# adapter_RX2189.net
KiCad netlist of a schematic drawn in EAGLE
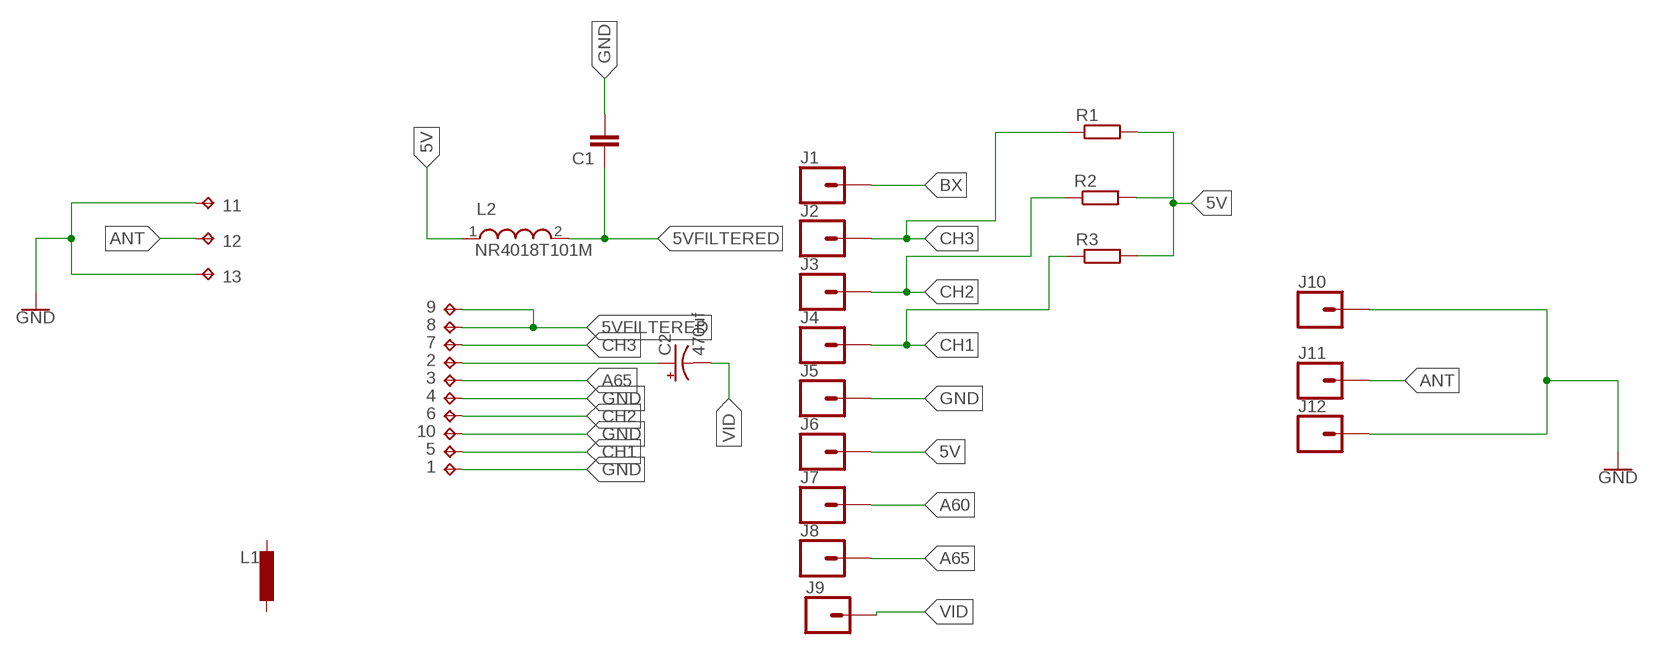
[diagram p0: schematic, sheet 1]

(export (version "E")
  (design (tool "Eeschema 10.0.6"))
  (components
    (comp (ref "1")
      (value "TPTP10SQ")
      (footprint "eagle-import:TP10SQ")
      (libsource (lib "eagle-import") (part "TPTP10SQ"))
    )
    (comp (ref "2")
      (value "TPTP10SQ")
      (footprint "eagle-import:TP10SQ")
      (libsource (lib "eagle-import") (part "TPTP10SQ"))
    )
    (comp (ref "3")
      (value "TPTP10SQ")
      (footprint "eagle-import:TP10SQ")
      (libsource (lib "eagle-import") (part "TPTP10SQ"))
    )
    (comp (ref "4")
      (value "TPTP10SQ")
      (footprint "eagle-import:TP10SQ")
      (libsource (lib "eagle-import") (part "TPTP10SQ"))
    )
    (comp (ref "5")
      (value "TPTP10SQ")
      (footprint "eagle-import:TP10SQ")
      (libsource (lib "eagle-import") (part "TPTP10SQ"))
    )
    (comp (ref "6")
      (value "TPTP10SQ")
      (footprint "eagle-import:TP10SQ")
      (libsource (lib "eagle-import") (part "TPTP10SQ"))
    )
    (comp (ref "7")
      (value "TPTP10SQ")
      (footprint "eagle-import:TP10SQ")
      (libsource (lib "eagle-import") (part "TPTP10SQ"))
    )
    (comp (ref "8")
      (value "TPTP10SQ")
      (footprint "eagle-import:TP10SQ")
      (libsource (lib "eagle-import") (part "TPTP10SQ"))
    )
    (comp (ref "9")
      (value "TPTP10SQ")
      (footprint "eagle-import:TP10SQ")
      (libsource (lib "eagle-import") (part "TPTP10SQ"))
    )
    (comp (ref "10")
      (value "TPTP10SQ")
      (footprint "eagle-import:TP10SQ")
      (libsource (lib "eagle-import") (part "TPTP10SQ"))
    )
    (comp (ref "11")
      (value "TPTP10SQ")
      (footprint "eagle-import:TP10SQ")
      (libsource (lib "eagle-import") (part "TPTP10SQ"))
    )
    (comp (ref "12")
      (value "TPTP10SQ")
      (footprint "eagle-import:TP10SQ")
      (libsource (lib "eagle-import") (part "TPTP10SQ"))
    )
    (comp (ref "13")
      (value "TPTP10SQ")
      (footprint "eagle-import:TP10SQ")
      (libsource (lib "eagle-import") (part "TPTP10SQ"))
    )
    (comp (ref "C1")
      (value "C-EUC1206K")
      (footprint "eagle-import:C1206K")
      (libsource (lib "eagle-import") (part "C-EUC1206K"))
    )
    (comp (ref "C2")
      (value "470uf")
      (footprint "eagle-import:EIA7343")
      (libsource (lib "eagle-import") (part "CAP_POL7343"))
    )
    (comp (ref "J1")
      (value "CONN_01PTH_NO_SILK_KIT")
      (footprint "eagle-import:1X01NS_KIT")
      (libsource (lib "eagle-import") (part "CONN_01PTH_NO_SILK_KIT"))
    )
    (comp (ref "J2")
      (value "CONN_01PTH_NO_SILK_KIT")
      (footprint "eagle-import:1X01NS_KIT")
      (libsource (lib "eagle-import") (part "CONN_01PTH_NO_SILK_KIT"))
    )
    (comp (ref "J3")
      (value "CONN_01PTH_NO_SILK_KIT")
      (footprint "eagle-import:1X01NS_KIT")
      (libsource (lib "eagle-import") (part "CONN_01PTH_NO_SILK_KIT"))
    )
    (comp (ref "J4")
      (value "CONN_01PTH_NO_SILK_KIT")
      (footprint "eagle-import:1X01NS_KIT")
      (libsource (lib "eagle-import") (part "CONN_01PTH_NO_SILK_KIT"))
    )
    (comp (ref "J5")
      (value "CONN_01PTH_NO_SILK_KIT")
      (footprint "eagle-import:1X01NS_KIT")
      (libsource (lib "eagle-import") (part "CONN_01PTH_NO_SILK_KIT"))
    )
    (comp (ref "J6")
      (value "CONN_01PTH_NO_SILK_KIT")
      (footprint "eagle-import:1X01NS_KIT")
      (libsource (lib "eagle-import") (part "CONN_01PTH_NO_SILK_KIT"))
    )
    (comp (ref "J7")
      (value "CONN_01PTH_NO_SILK_KIT")
      (footprint "eagle-import:1X01NS_KIT")
      (libsource (lib "eagle-import") (part "CONN_01PTH_NO_SILK_KIT"))
    )
    (comp (ref "J8")
      (value "CONN_01PTH_NO_SILK_KIT")
      (footprint "eagle-import:1X01NS_KIT")
      (libsource (lib "eagle-import") (part "CONN_01PTH_NO_SILK_KIT"))
    )
    (comp (ref "J9")
      (value "CONN_01PTH_NO_SILK_KIT")
      (footprint "eagle-import:1X01NS_KIT")
      (libsource (lib "eagle-import") (part "CONN_01PTH_NO_SILK_KIT"))
    )
    (comp (ref "J10")
      (value "CONN_01PTH_NO_SILK_KIT")
      (footprint "eagle-import:1X01NS_KIT")
      (libsource (lib "eagle-import") (part "CONN_01PTH_NO_SILK_KIT"))
    )
    (comp (ref "J11")
      (value "CONN_01PTH_NO_SILK_KIT")
      (footprint "eagle-import:1X01NS_KIT")
      (libsource (lib "eagle-import") (part "CONN_01PTH_NO_SILK_KIT"))
    )
    (comp (ref "J12")
      (value "CONN_01PTH_NO_SILK_KIT")
      (footprint "eagle-import:1X01NS_KIT")
      (libsource (lib "eagle-import") (part "CONN_01PTH_NO_SILK_KIT"))
    )
    (comp (ref "L1")
      (value "L-EUWE-TPC")
      (footprint "eagle-import:POWER-CHOKE_WE-TPC")
      (libsource (lib "eagle-import") (part "L-EUWE-TPC"))
    )
    (comp (ref "L2")
      (value "NR4018T101M")
      (footprint "eagle-import:INDM4949X200N")
      (fields (field (name "MF") "Taiyo Yuden") (field (name "MP") "NRS5020T220MMGJ"))
      (libsource (lib "eagle-import") (part "NRS5020T220MMGJ"))
    )
    (comp (ref "R1")
      (value "R-EU_R0603")
      (footprint "eagle-import:R0603")
      (libsource (lib "eagle-import") (part "R-EU_R0603"))
    )
    (comp (ref "R2")
      (value "R-EU_R0603")
      (footprint "eagle-import:R0603")
      (libsource (lib "eagle-import") (part "R-EU_R0603"))
    )
    (comp (ref "R3")
      (value "R-EU_R0603")
      (footprint "eagle-import:R0603")
      (libsource (lib "eagle-import") (part "R-EU_R0603"))
    )
  )
  (nets
    (net (code "1") (name "5V") (class "Default")
      (node (ref "J6") (pin "1") (pinfunction "1_1") (pintype "passive"))
      (node (ref "L2") (pin "1") (pinfunction "1_1") (pintype "passive"))
      (node (ref "R1") (pin "2") (pinfunction "2_2") (pintype "passive"))
      (node (ref "R2") (pin "2") (pinfunction "2_2") (pintype "passive"))
      (node (ref "R3") (pin "2") (pinfunction "2_2") (pintype "passive"))
    )
    (net (code "2") (name "5VFILTERED") (class "Default")
      (node (ref "8") (pin "TP") (pinfunction "TP_TP") (pintype "input"))
      (node (ref "9") (pin "TP") (pinfunction "TP_TP") (pintype "input"))
      (node (ref "C1") (pin "1") (pinfunction "1_1") (pintype "passive"))
      (node (ref "L2") (pin "2") (pinfunction "2_2") (pintype "passive"))
    )
    (net (code "3") (name "A60") (class "Default")
      (node (ref "J7") (pin "1") (pinfunction "1_1") (pintype "passive"))
    )
    (net (code "4") (name "A65") (class "Default")
      (node (ref "3") (pin "TP") (pinfunction "TP_TP") (pintype "input"))
      (node (ref "J8") (pin "1") (pinfunction "1_1") (pintype "passive"))
    )
    (net (code "5") (name "ANT") (class "Default")
      (node (ref "12") (pin "TP") (pinfunction "TP_TP") (pintype "input"))
      (node (ref "J11") (pin "1") (pinfunction "1_1") (pintype "passive"))
    )
    (net (code "6") (name "BX") (class "Default")
      (node (ref "J1") (pin "1") (pinfunction "1_1") (pintype "passive"))
    )
    (net (code "7") (name "CH1") (class "Default")
      (node (ref "5") (pin "TP") (pinfunction "TP_TP") (pintype "input"))
      (node (ref "J4") (pin "1") (pinfunction "1_1") (pintype "passive"))
      (node (ref "R3") (pin "1") (pinfunction "1_1") (pintype "passive"))
    )
    (net (code "8") (name "CH2") (class "Default")
      (node (ref "6") (pin "TP") (pinfunction "TP_TP") (pintype "input"))
      (node (ref "J3") (pin "1") (pinfunction "1_1") (pintype "passive"))
      (node (ref "R2") (pin "1") (pinfunction "1_1") (pintype "passive"))
    )
    (net (code "9") (name "CH3") (class "Default")
      (node (ref "7") (pin "TP") (pinfunction "TP_TP") (pintype "input"))
      (node (ref "J2") (pin "1") (pinfunction "1_1") (pintype "passive"))
      (node (ref "R1") (pin "1") (pinfunction "1_1") (pintype "passive"))
    )
    (net (code "10") (name "GND") (class "Default")
      (node (ref "1") (pin "TP") (pinfunction "TP_TP") (pintype "input"))
      (node (ref "10") (pin "TP") (pinfunction "TP_TP") (pintype "input"))
      (node (ref "11") (pin "TP") (pinfunction "TP_TP") (pintype "input"))
      (node (ref "13") (pin "TP") (pinfunction "TP_TP") (pintype "input"))
      (node (ref "4") (pin "TP") (pinfunction "TP_TP") (pintype "input"))
      (node (ref "C1") (pin "2") (pinfunction "2_2") (pintype "passive"))
      (node (ref "J10") (pin "1") (pinfunction "1_1") (pintype "passive"))
      (node (ref "J12") (pin "1") (pinfunction "1_1") (pintype "passive"))
      (node (ref "J5") (pin "1") (pinfunction "1_1") (pintype "passive"))
    )
    (net (code "11") (name "Net-(C2-+)") (class "Default")
      (node (ref "2") (pin "TP") (pinfunction "TP_TP") (pintype "input"))
      (node (ref "C2") (pin "A") (pinfunction "+_A") (pintype "passive"))
    )
    (net (code "12") (name "VID") (class "Default")
      (node (ref "C2") (pin "C") (pinfunction "-_C") (pintype "passive"))
      (node (ref "J9") (pin "1") (pinfunction "1_1") (pintype "passive"))
    )
    (net (code "13") (name "unconnected-(L1-Pad1)") (class "Default")
      (node (ref "L1") (pin "1") (pinfunction "1_1") (pintype "passive"))
    )
    (net (code "14") (name "unconnected-(L1-Pad2)") (class "Default")
      (node (ref "L1") (pin "2") (pinfunction "2_2") (pintype "passive"))
    )
  )
)
